# scarf.net
KiCad netlist of a schematic drawn in EAGLE
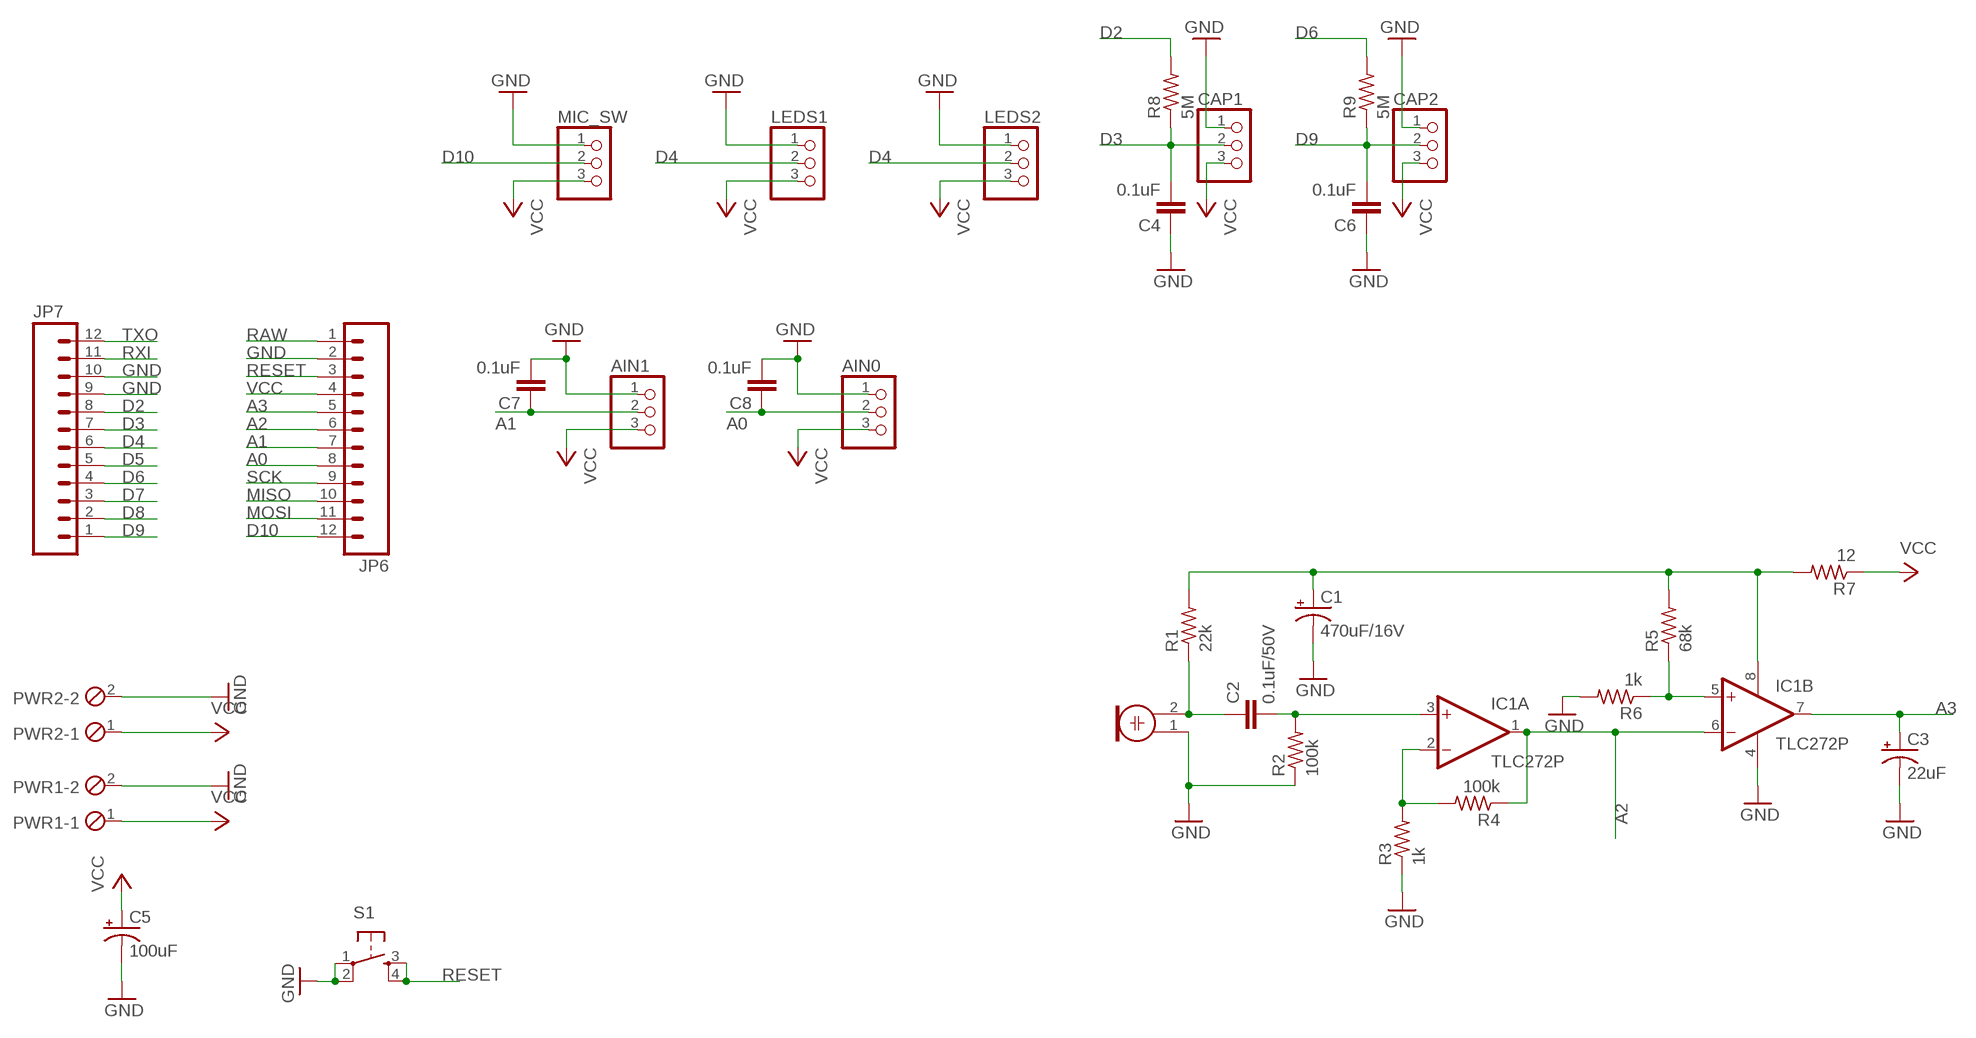
[diagram p0: schematic, sheet 1]

(export (version "E")
  (design (tool "Eeschema 10.0.6"))
  (components
    (comp (ref "AIN0")
      (value "HEADER-1X3ROUND")
      (footprint "eagle-import:1X03_ROUND")
      (libsource (lib "eagle-import") (part "HEADER-1X3ROUND"))
    )
    (comp (ref "AIN1")
      (value "HEADER-1X3ROUND")
      (footprint "eagle-import:1X03_ROUND")
      (libsource (lib "eagle-import") (part "HEADER-1X3ROUND"))
    )
    (comp (ref "C1")
      (value "470uF/16V")
      (footprint "eagle-import:E2,5-6")
      (libsource (lib "eagle-import") (part "CPOL-USE2.5-6"))
    )
    (comp (ref "C2")
      (value "0.1uF/50V")
      (footprint "eagle-import:C050-025X075")
      (libsource (lib "eagle-import") (part "C-EU050-025X075"))
    )
    (comp (ref "C3")
      (value "22uF")
      (footprint "eagle-import:E2,5-6")
      (libsource (lib "eagle-import") (part "CPOL-USE2.5-6"))
    )
    (comp (ref "C4")
      (value "0.1uF")
      (footprint "eagle-import:C025-025X050")
      (libsource (lib "eagle-import") (part "C-EU025-025X050"))
    )
    (comp (ref "C5")
      (value "100uF")
      (footprint "eagle-import:E3,5-8")
      (libsource (lib "eagle-import") (part "CPOL-USE3.5-8"))
    )
    (comp (ref "C6")
      (value "0.1uF")
      (footprint "eagle-import:C025-025X050")
      (libsource (lib "eagle-import") (part "C-EU025-025X050"))
    )
    (comp (ref "C7")
      (value "0.1uF")
      (footprint "eagle-import:C025-025X050")
      (libsource (lib "eagle-import") (part "C-EU025-025X050"))
    )
    (comp (ref "C8")
      (value "0.1uF")
      (footprint "eagle-import:C025-025X050")
      (libsource (lib "eagle-import") (part "C-EU025-025X050"))
    )
    (comp (ref "CAP1")
      (value "HEADER-1X3ROUND")
      (footprint "eagle-import:1X03_ROUND")
      (libsource (lib "eagle-import") (part "HEADER-1X3ROUND"))
    )
    (comp (ref "CAP2")
      (value "HEADER-1X3ROUND")
      (footprint "eagle-import:1X03_ROUND")
      (libsource (lib "eagle-import") (part "HEADER-1X3ROUND"))
    )
    (comp (ref "IC1")
      (value "TLC272P")
      (footprint "eagle-import:DIL08")
      (libsource (lib "eagle-import") (part "TLC272P"))
    )
    (comp (ref "JP6")
      (value "M12PTH")
      (footprint "eagle-import:1X12")
      (libsource (lib "eagle-import") (part "M12PTH"))
    )
    (comp (ref "JP7")
      (value "M12PTH")
      (footprint "eagle-import:1X12")
      (libsource (lib "eagle-import") (part "M12PTH"))
    )
    (comp (ref "LEDS1")
      (value "PINHD-1X3")
      (footprint "eagle-import:1X03")
      (libsource (lib "eagle-import") (part "PINHD-1X3"))
    )
    (comp (ref "LEDS2")
      (value "PINHD-1X3")
      (footprint "eagle-import:1X03")
      (libsource (lib "eagle-import") (part "PINHD-1X3"))
    )
    (comp (ref "M1")
      (value "ELECTRET_MICROPHON-WM.64PN")
      (footprint "eagle-import:WM-64PN")
      (libsource (lib "eagle-import") (part "ELECTRET_MICROPHON-WM.64PN"))
    )
    (comp (ref "MIC_SW")
      (value "HEADER-1X3ROUND")
      (footprint "eagle-import:1X03_ROUND")
      (libsource (lib "eagle-import") (part "HEADER-1X3ROUND"))
    )
    (comp (ref "PWR1")
      (value "MPT2")
      (footprint "eagle-import:2POL254")
      (libsource (lib "eagle-import") (part "MPT2"))
    )
    (comp (ref "PWR2")
      (value "MPT2")
      (footprint "eagle-import:2POL254")
      (libsource (lib "eagle-import") (part "MPT2"))
    )
    (comp (ref "R1")
      (value "22k")
      (footprint "eagle-import:0204_7")
      (libsource (lib "eagle-import") (part "R-US_0204/7"))
    )
    (comp (ref "R2")
      (value "100k")
      (footprint "eagle-import:0204_7")
      (libsource (lib "eagle-import") (part "R-US_0204/7"))
    )
    (comp (ref "R3")
      (value "1k")
      (footprint "eagle-import:0204_7")
      (libsource (lib "eagle-import") (part "R-US_0204/7"))
    )
    (comp (ref "R4")
      (value "100k")
      (footprint "eagle-import:0204_7")
      (libsource (lib "eagle-import") (part "R-US_0204/7"))
    )
    (comp (ref "R5")
      (value "68k")
      (footprint "eagle-import:0204_7")
      (libsource (lib "eagle-import") (part "R-US_0204/7"))
    )
    (comp (ref "R6")
      (value "1k")
      (footprint "eagle-import:0204_7")
      (libsource (lib "eagle-import") (part "R-US_0204/7"))
    )
    (comp (ref "R7")
      (value "12")
      (footprint "eagle-import:0204_7")
      (libsource (lib "eagle-import") (part "R-US_0204/7"))
    )
    (comp (ref "R8")
      (value "5M")
      (footprint "eagle-import:0204_7")
      (libsource (lib "eagle-import") (part "R-US_0204/7"))
    )
    (comp (ref "R9")
      (value "5M")
      (footprint "eagle-import:0204_7")
      (libsource (lib "eagle-import") (part "R-US_0204/7"))
    )
    (comp (ref "S1")
      (value "TAC_SWITCHPTH")
      (footprint "eagle-import:TACTILE-PTH")
      (libsource (lib "eagle-import") (part "TAC_SWITCHPTH"))
    )
  )
  (nets
    (net (code "1") (name "/A0") (class "Default")
      (node (ref "AIN0") (pin "2") (pinfunction "2_2") (pintype "passive"))
      (node (ref "C8") (pin "1") (pinfunction "1_1") (pintype "passive"))
      (node (ref "JP6") (pin "8") (pinfunction "8_8") (pintype "passive"))
    )
    (net (code "2") (name "/A1") (class "Default")
      (node (ref "AIN1") (pin "2") (pinfunction "2_2") (pintype "passive"))
      (node (ref "C7") (pin "1") (pinfunction "1_1") (pintype "passive"))
      (node (ref "JP6") (pin "7") (pinfunction "7_7") (pintype "passive"))
    )
    (net (code "3") (name "/A2") (class "Default")
      (node (ref "IC1") (pin "1") (pinfunction "OUT_1") (pintype "output"))
      (node (ref "IC1") (pin "6") (pinfunction "-IN_6") (pintype "input"))
      (node (ref "JP6") (pin "6") (pinfunction "6_6") (pintype "passive"))
      (node (ref "R4") (pin "1") (pinfunction "1_1") (pintype "passive"))
    )
    (net (code "4") (name "/A3") (class "Default")
      (node (ref "C3") (pin "+") (pinfunction "+_+") (pintype "passive"))
      (node (ref "IC1") (pin "7") (pinfunction "OUT_7") (pintype "output"))
      (node (ref "JP6") (pin "5") (pinfunction "5_5") (pintype "passive"))
    )
    (net (code "5") (name "/D2") (class "Default")
      (node (ref "JP7") (pin "8") (pinfunction "8_8") (pintype "passive"))
      (node (ref "R8") (pin "2") (pinfunction "2_2") (pintype "passive"))
    )
    (net (code "6") (name "/D3") (class "Default")
      (node (ref "C4") (pin "2") (pinfunction "2_2") (pintype "passive"))
      (node (ref "CAP1") (pin "2") (pinfunction "2_2") (pintype "passive"))
      (node (ref "JP7") (pin "7") (pinfunction "7_7") (pintype "passive"))
      (node (ref "R8") (pin "1") (pinfunction "1_1") (pintype "passive"))
    )
    (net (code "7") (name "/D4") (class "Default")
      (node (ref "JP7") (pin "6") (pinfunction "6_6") (pintype "passive"))
      (node (ref "LEDS1") (pin "2") (pinfunction "2_2") (pintype "passive"))
      (node (ref "LEDS2") (pin "2") (pinfunction "2_2") (pintype "passive"))
    )
    (net (code "8") (name "/D5") (class "Default")
      (node (ref "JP7") (pin "5") (pinfunction "5_5") (pintype "passive"))
    )
    (net (code "9") (name "/D6") (class "Default")
      (node (ref "JP7") (pin "4") (pinfunction "4_4") (pintype "passive"))
      (node (ref "R9") (pin "2") (pinfunction "2_2") (pintype "passive"))
    )
    (net (code "10") (name "/D7") (class "Default")
      (node (ref "JP7") (pin "3") (pinfunction "3_3") (pintype "passive"))
    )
    (net (code "11") (name "/D8") (class "Default")
      (node (ref "JP7") (pin "2") (pinfunction "2_2") (pintype "passive"))
    )
    (net (code "12") (name "/D9") (class "Default")
      (node (ref "C6") (pin "2") (pinfunction "2_2") (pintype "passive"))
      (node (ref "CAP2") (pin "2") (pinfunction "2_2") (pintype "passive"))
      (node (ref "JP7") (pin "1") (pinfunction "1_1") (pintype "passive"))
      (node (ref "R9") (pin "1") (pinfunction "1_1") (pintype "passive"))
    )
    (net (code "13") (name "/D10") (class "Default")
      (node (ref "JP6") (pin "12") (pinfunction "12_12") (pintype "passive"))
      (node (ref "MIC_SW") (pin "2") (pinfunction "2_2") (pintype "passive"))
    )
    (net (code "14") (name "/MISO") (class "Default")
      (node (ref "JP6") (pin "10") (pinfunction "10_10") (pintype "passive"))
    )
    (net (code "15") (name "/MOSI") (class "Default")
      (node (ref "JP6") (pin "11") (pinfunction "11_11") (pintype "passive"))
    )
    (net (code "16") (name "/RAW") (class "Default")
      (node (ref "JP6") (pin "1") (pinfunction "1_1") (pintype "passive"))
    )
    (net (code "17") (name "/RESET") (class "Default")
      (node (ref "JP6") (pin "3") (pinfunction "3_3") (pintype "passive"))
      (node (ref "S1") (pin "3") (pinfunction "3_3") (pintype "passive"))
      (node (ref "S1") (pin "4") (pinfunction "4_4") (pintype "passive"))
    )
    (net (code "18") (name "/RXI") (class "Default")
      (node (ref "JP7") (pin "11") (pinfunction "11_11") (pintype "passive"))
    )
    (net (code "19") (name "/SCK") (class "Default")
      (node (ref "JP6") (pin "9") (pinfunction "9_9") (pintype "passive"))
    )
    (net (code "20") (name "/TXO") (class "Default")
      (node (ref "JP7") (pin "12") (pinfunction "12_12") (pintype "passive"))
    )
    (net (code "21") (name "GND") (class "Default")
      (node (ref "AIN0") (pin "1") (pinfunction "1_1") (pintype "passive"))
      (node (ref "AIN1") (pin "1") (pinfunction "1_1") (pintype "passive"))
      (node (ref "C1") (pin "-") (pinfunction "-_-") (pintype "passive"))
      (node (ref "C3") (pin "-") (pinfunction "-_-") (pintype "passive"))
      (node (ref "C4") (pin "1") (pinfunction "1_1") (pintype "passive"))
      (node (ref "C5") (pin "-") (pinfunction "-_-") (pintype "passive"))
      (node (ref "C6") (pin "1") (pinfunction "1_1") (pintype "passive"))
      (node (ref "C7") (pin "2") (pinfunction "2_2") (pintype "passive"))
      (node (ref "C8") (pin "2") (pinfunction "2_2") (pintype "passive"))
      (node (ref "CAP1") (pin "1") (pinfunction "1_1") (pintype "passive"))
      (node (ref "CAP2") (pin "1") (pinfunction "1_1") (pintype "passive"))
      (node (ref "IC1") (pin "4") (pinfunction "V-_4") (pintype "power_in"))
      (node (ref "JP6") (pin "2") (pinfunction "2_2") (pintype "passive"))
      (node (ref "JP7") (pin "10") (pinfunction "10_10") (pintype "passive"))
      (node (ref "JP7") (pin "9") (pinfunction "9_9") (pintype "passive"))
      (node (ref "LEDS1") (pin "1") (pinfunction "1_1") (pintype "passive"))
      (node (ref "LEDS2") (pin "1") (pinfunction "1_1") (pintype "passive"))
      (node (ref "M1") (pin "1") (pinfunction "1_1") (pintype "passive"))
      (node (ref "MIC_SW") (pin "1") (pinfunction "1_1") (pintype "passive"))
      (node (ref "PWR1") (pin "2") (pinfunction "1_2") (pintype "passive"))
      (node (ref "PWR2") (pin "2") (pinfunction "1_2") (pintype "passive"))
      (node (ref "R2") (pin "1") (pinfunction "1_1") (pintype "passive"))
      (node (ref "R3") (pin "1") (pinfunction "1_1") (pintype "passive"))
      (node (ref "R6") (pin "2") (pinfunction "2_2") (pintype "passive"))
      (node (ref "S1") (pin "1") (pinfunction "1_1") (pintype "passive"))
      (node (ref "S1") (pin "2") (pinfunction "2_2") (pintype "passive"))
    )
    (net (code "22") (name "Net-(C2-Pad1)") (class "Default")
      (node (ref "C2") (pin "1") (pinfunction "1_1") (pintype "passive"))
      (node (ref "M1") (pin "2") (pinfunction "2_2") (pintype "passive"))
      (node (ref "R1") (pin "1") (pinfunction "1_1") (pintype "passive"))
    )
    (net (code "23") (name "Net-(IC1A-+IN)") (class "Default")
      (node (ref "C2") (pin "2") (pinfunction "2_2") (pintype "passive"))
      (node (ref "IC1") (pin "3") (pinfunction "+IN_3") (pintype "input"))
      (node (ref "R2") (pin "2") (pinfunction "2_2") (pintype "passive"))
    )
    (net (code "24") (name "Net-(IC1A--IN)") (class "Default")
      (node (ref "IC1") (pin "2") (pinfunction "-IN_2") (pintype "input"))
      (node (ref "R3") (pin "2") (pinfunction "2_2") (pintype "passive"))
      (node (ref "R4") (pin "2") (pinfunction "2_2") (pintype "passive"))
    )
    (net (code "25") (name "Net-(IC1B-+IN)") (class "Default")
      (node (ref "IC1") (pin "5") (pinfunction "+IN_5") (pintype "input"))
      (node (ref "R5") (pin "1") (pinfunction "1_1") (pintype "passive"))
      (node (ref "R6") (pin "1") (pinfunction "1_1") (pintype "passive"))
    )
    (net (code "26") (name "Net-(IC1C-V+)") (class "Default")
      (node (ref "C1") (pin "+") (pinfunction "+_+") (pintype "passive"))
      (node (ref "IC1") (pin "8") (pinfunction "V+_8") (pintype "power_in"))
      (node (ref "R1") (pin "2") (pinfunction "2_2") (pintype "passive"))
      (node (ref "R5") (pin "2") (pinfunction "2_2") (pintype "passive"))
      (node (ref "R7") (pin "2") (pinfunction "2_2") (pintype "passive"))
    )
    (net (code "27") (name "VCC") (class "Default")
      (node (ref "AIN0") (pin "3") (pinfunction "3_3") (pintype "passive"))
      (node (ref "AIN1") (pin "3") (pinfunction "3_3") (pintype "passive"))
      (node (ref "C5") (pin "+") (pinfunction "+_+") (pintype "passive"))
      (node (ref "CAP1") (pin "3") (pinfunction "3_3") (pintype "passive"))
      (node (ref "CAP2") (pin "3") (pinfunction "3_3") (pintype "passive"))
      (node (ref "JP6") (pin "4") (pinfunction "4_4") (pintype "passive"))
      (node (ref "LEDS1") (pin "3") (pinfunction "3_3") (pintype "passive"))
      (node (ref "LEDS2") (pin "3") (pinfunction "3_3") (pintype "passive"))
      (node (ref "MIC_SW") (pin "3") (pinfunction "3_3") (pintype "passive"))
      (node (ref "PWR1") (pin "1") (pinfunction "1_1") (pintype "passive"))
      (node (ref "PWR2") (pin "1") (pinfunction "1_1") (pintype "passive"))
      (node (ref "R7") (pin "1") (pinfunction "1_1") (pintype "passive"))
    )
  )
)
